# POWER.net
KiCad netlist of a schematic drawn in Altium Designer
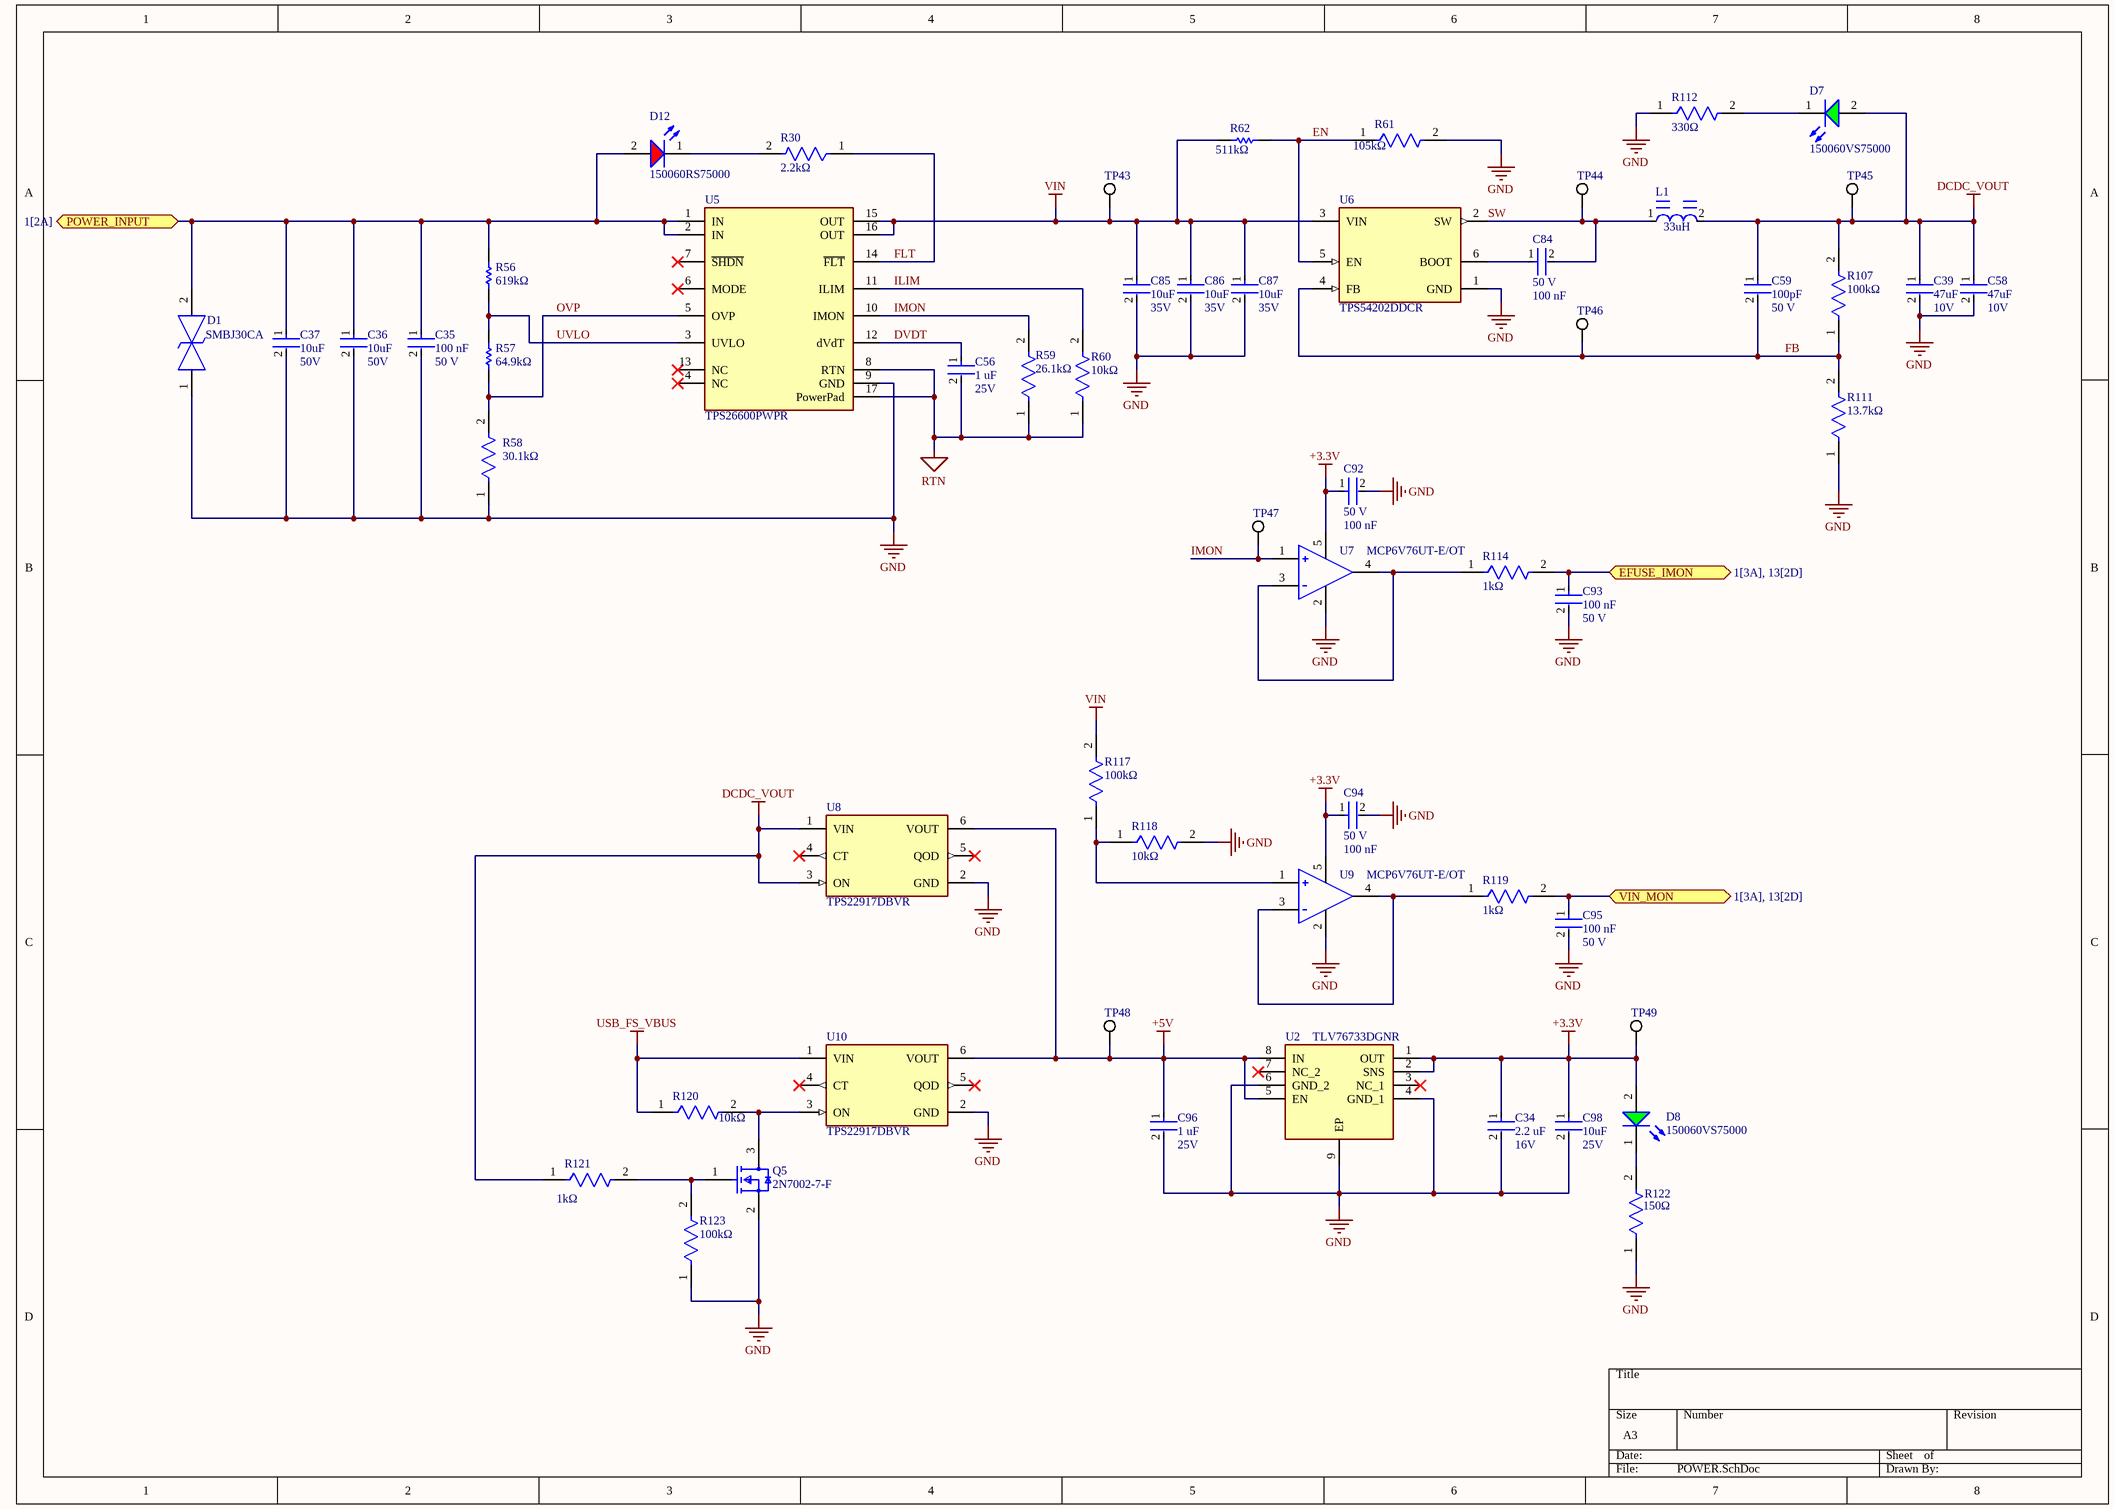
[diagram p0: POWER.SchDoc]

(export (version "E")
  (design (tool "Eeschema 10.0.6"))
  (components
    (comp (ref "C34")
      (value "CL10A225KO8NNNC")
      (footprint "FP-CL10-IPC_B")
      (description "Cap Ceramic 2.2uF 16V X5R ±10% Pad SMD 0603 +85°C T/R")
      (fields
        (field (name "CAPACITANCE") "2.2 uF")
        (field (name "VOLTAGE RATING") "16V")
        (field (name "TOLERANCE") "10%")
        (field (name "VOLTAGE") "16V")
      )
      (libsource (lib "Altium Content Vault") (part "b4654b650e69147ec39a6b967a45e02"))
    )
    (comp (ref "C35")
      (value "100 nF")
      (footprint "FP-C0603C-CF-IPC_B")
      (description "CAP CER 0.1UF 50V 20% X7R 0603")
      (fields
        (field (name "VOLTAGE RATING") "50 V")
        (field (name "MANUFACTURER PART NUMBER") "C0603C104M5RACTU")
        (field (name "MANUFACTURER") "KEMET")
      )
      (libsource (lib "Altium Content Vault") (part "b4654b650e69147ec39a6b967a45e02"))
    )
    (comp (ref "C36")
      (value "CL31A106KBHNNNE")
      (footprint "FP-CL31-IPC_B")
      (description "CAP CER 10UF 50V X5R 1206")
      (fields
        (field (name "TOLERANCE") "10%")
        (field (name "MANUFACTURER") "Samsung")
        (field (name "VOLTAGE") "50V")
        (field (name "CAPACITANCE") "10uF")
      )
      (libsource (lib "Altium Content Vault") (part "11868f565c42a9108669ba33697ecf6"))
    )
    (comp (ref "C37")
      (value "CL31A106KBHNNNE")
      (footprint "FP-CL31-IPC_B")
      (description "CAP CER 10UF 50V X5R 1206")
      (fields
        (field (name "TOLERANCE") "10%")
        (field (name "MANUFACTURER") "Samsung")
        (field (name "VOLTAGE") "50V")
        (field (name "CAPACITANCE") "10uF")
      )
      (libsource (lib "Altium Content Vault") (part "11868f565c42a9108669ba33697ecf6"))
    )
    (comp (ref "C39")
      (value "GRM32ER71A476KE15L")
      (footprint "FP-GRM32E-0_3-0_2-IPC_B")
      (description "Chip Multilayer Ceramic Capacitors for General Purpose, 1210, 47uF, X7R, 15%, 10%, 10V")
      (fields
        (field (name "VOLTAGE RATING") "10V")
        (field (name "TOLERANCE") "10%")
        (field (name "VOLTAGE") "10V")
        (field (name "CAPACITANCE") "47uF")
      )
      (libsource (lib "Altium Content Vault") (part "02cd4be3c70576c341d710602a673aa"))
    )
    (comp (ref "C56")
      (value "GCM188R71E105KA64D")
      (footprint "FP-GCM188-0_1-IPC_B")
      (fields
        (field (name "TOLERANCE") "10%")
        (field (name "CAPACITANCE") "1 uF")
        (field (name "VOLTAGE RATING") "25V")
        (field (name "VOLTAGE") "25V")
      )
      (libsource (lib "Altium Content Vault") (part "02cd4be3c70576c341d710602a673aa"))
    )
    (comp (ref "C58")
      (value "GRM32ER71A476KE15L")
      (footprint "FP-GRM32E-0_3-0_2-IPC_B")
      (description "Chip Multilayer Ceramic Capacitors for General Purpose, 1210, 47uF, X7R, 15%, 10%, 10V")
      (fields
        (field (name "VOLTAGE RATING") "10V")
        (field (name "TOLERANCE") "10%")
        (field (name "VOLTAGE") "10V")
        (field (name "CAPACITANCE") "47uF")
      )
      (libsource (lib "Altium Content Vault") (part "02cd4be3c70576c341d710602a673aa"))
    )
    (comp (ref "C59")
      (value "C0603C101J5GACTU")
      (footprint "FP-C0603C-CF-IPC_B")
      (description "CAP CER 100PF 50V C0G/NP0 0603")
      (fields
        (field (name "VOLTAGE RATING") "50 V")
        (field (name "TOLERANCE") "0.05")
        (field (name "MANUFACTURER") "KEMET")
        (field (name "CAPACITANCE") "100pF")
      )
      (libsource (lib "Altium Content Vault") (part "b4654b650e69147ec39a6b967a45e02"))
    )
    (comp (ref "C84")
      (value "100 nF")
      (footprint "FP-C0603C-CF-IPC_B")
      (description "CAP CER 0.1UF 50V 20% X7R 0603")
      (fields
        (field (name "VOLTAGE RATING") "50 V")
        (field (name "MANUFACTURER PART NUMBER") "C0603C104M5RACTU")
        (field (name "MANUFACTURER") "KEMET")
      )
      (libsource (lib "Altium Content Vault") (part "b4654b650e69147ec39a6b967a45e02"))
    )
    (comp (ref "C85")
      (value "GRM21BR6YA106KE43L")
      (footprint "FP-GRM21B-0_2-e0_2_0_7-IPC_B")
      (description "Chip Multilayer Ceramic Capacitors for General Purpose, 0805, 10uF, X5R, 15%, 10%, 35V")
      (fields
        (field (name "TOLERANCE") "10%")
        (field (name "CAPACITANCE") "10uF")
        (field (name "VOLTAGE RATING") "35V")
      )
      (libsource (lib "Altium Content Vault") (part "b4654b650e69147ec39a6b967a45e02"))
    )
    (comp (ref "C86")
      (value "GRM21BR6YA106KE43L")
      (footprint "FP-GRM21B-0_2-e0_2_0_7-IPC_B")
      (description "Chip Multilayer Ceramic Capacitors for General Purpose, 0805, 10uF, X5R, 15%, 10%, 35V")
      (fields
        (field (name "TOLERANCE") "10%")
        (field (name "CAPACITANCE") "10uF")
        (field (name "VOLTAGE RATING") "35V")
      )
      (libsource (lib "Altium Content Vault") (part "b4654b650e69147ec39a6b967a45e02"))
    )
    (comp (ref "C87")
      (value "GRM21BR6YA106KE43L")
      (footprint "FP-GRM21B-0_2-e0_2_0_7-IPC_B")
      (description "Chip Multilayer Ceramic Capacitors for General Purpose, 0805, 10uF, X5R, 15%, 10%, 35V")
      (fields
        (field (name "TOLERANCE") "10%")
        (field (name "CAPACITANCE") "10uF")
        (field (name "VOLTAGE RATING") "35V")
      )
      (libsource (lib "Altium Content Vault") (part "b4654b650e69147ec39a6b967a45e02"))
    )
    (comp (ref "C92")
      (value "100 nF")
      (footprint "FP-C0603C-CF-IPC_B")
      (description "CAP CER 0.1UF 50V 20% X7R 0603")
      (fields
        (field (name "VOLTAGE RATING") "50 V")
        (field (name "MANUFACTURER PART NUMBER") "C0603C104M5RACTU")
        (field (name "MANUFACTURER") "KEMET")
      )
      (libsource (lib "Altium Content Vault") (part "b4654b650e69147ec39a6b967a45e02"))
    )
    (comp (ref "C93")
      (value "100 nF")
      (footprint "FP-C0603C-CF-IPC_B")
      (description "CAP CER 0.1UF 50V 20% X7R 0603")
      (fields
        (field (name "VOLTAGE RATING") "50 V")
        (field (name "MANUFACTURER PART NUMBER") "C0603C104M5RACTU")
        (field (name "MANUFACTURER") "KEMET")
      )
      (libsource (lib "Altium Content Vault") (part "b4654b650e69147ec39a6b967a45e02"))
    )
    (comp (ref "C94")
      (value "100 nF")
      (footprint "FP-C0603C-CF-IPC_B")
      (description "CAP CER 0.1UF 50V 20% X7R 0603")
      (fields
        (field (name "VOLTAGE RATING") "50 V")
        (field (name "MANUFACTURER PART NUMBER") "C0603C104M5RACTU")
        (field (name "MANUFACTURER") "KEMET")
      )
      (libsource (lib "Altium Content Vault") (part "b4654b650e69147ec39a6b967a45e02"))
    )
    (comp (ref "C95")
      (value "100 nF")
      (footprint "FP-C0603C-CF-IPC_B")
      (description "CAP CER 0.1UF 50V 20% X7R 0603")
      (fields
        (field (name "VOLTAGE RATING") "50 V")
        (field (name "MANUFACTURER PART NUMBER") "C0603C104M5RACTU")
        (field (name "MANUFACTURER") "KEMET")
      )
      (libsource (lib "Altium Content Vault") (part "b4654b650e69147ec39a6b967a45e02"))
    )
    (comp (ref "C96")
      (value "GCM188R71E105KA64D")
      (footprint "FP-GCM188-0_1-IPC_B")
      (fields
        (field (name "TOLERANCE") "10%")
        (field (name "CAPACITANCE") "1 uF")
        (field (name "VOLTAGE RATING") "25V")
        (field (name "VOLTAGE") "25V")
      )
      (libsource (lib "Altium Content Vault") (part "02cd4be3c70576c341d710602a673aa"))
    )
    (comp (ref "C98")
      (value "C1608X5R1E106M080AC")
      (footprint "FP-C1608-080-IPC_B")
      (description "CAP CER 10UF 25V X5R 0603")
      (fields
        (field (name "VOLTAGE RATING") "25V")
        (field (name "TOLERANCE") "20%")
        (field (name "CAPACITANCE") "10uF")
      )
      (libsource (lib "Altium Content Vault") (part "11868f565c42a9108669ba33697ecf6"))
    )
    (comp (ref "D1")
      (value "SMBJ30CA")
      (footprint "SamacSys:DIOM5436X244N")
      (description "TVS Diode (Bi-directional)")
      (fields (field (name "MOUSER PART NUMBER") "576-SMBJ30CA"))
      (libsource (lib "*") (part "SMBJ30CA"))
    )
    (comp (ref "D7")
      (value "150060VS75000")
      (footprint "WL-SMCW_0603_150060xx75000")
      (libsource (lib "Altium Content Vault") (part "LED_Green_2A-1K"))
    )
    (comp (ref "D8")
      (value "150060VS75000")
      (footprint "WL-SMCW_0603_150060xx75000")
      (libsource (lib "Altium Content Vault") (part "LED_Green_2A-1K"))
    )
    (comp (ref "D12")
      (value "150060RS75000")
      (footprint "WL-SMCW_0603_150060xx75000")
      (libsource (lib "Altium Content Vault") (part "LED_Red_2A-1K"))
    )
    (comp (ref "L1")
      (value "SRR1280-330M")
      (footprint "FP-SRR1280-MFG")
      (description "FIXED IND 33UH 3.5A 57 MOHM SMD")
      (fields (field (name "INDUCTANCE") "33uH") (field (name "TOLERANCE") "20%"))
      (libsource (lib "Altium Content Vault") (part "6d0fbef048cab01dc475e6ab11ab505"))
    )
    (comp (ref "Q5")
      (value "2N7002-7-F")
      (footprint "FP-SOT23-IPC_A")
      (description "MOSFET N-CH 60V 115MA SOT23-3")
      (fields (field (name "VOLTAGE") "60V"))
      (libsource (lib "Altium Content Vault") (part "3b9c635fedb024a5347a57b145af9cc"))
    )
    (comp (ref "R30")
      (value "AC0603FR-072K2L")
      (footprint "FP-AC0603-IPC_B")
      (description "RES 2.2KΩ 1.00% 0.1W 0603")
      (fields (field (name "TOLERANCE") "1%") (field (name "RESISTANCE") "2.2kΩ"))
      (libsource (lib "Altium Content Vault") (part "1029c3af85768c4190bb7ad29bc67b5"))
    )
    (comp (ref "R56")
      (value "ERJ-3EKF6193V")
      (footprint "RESC1608X55X30ML15T15")
      (fields (field (name "MANUFACTURER") "Panasonic") (field (name "RESISTANCE") "619kΩ"))
      (libsource (lib "Altium Content Vault") (part "RES"))
    )
    (comp (ref "R57")
      (value "ERJ-3EKF6492V")
      (footprint "RESC1608X55X30ML15T15")
      (fields (field (name "MANUFACTURER") "Panasonic") (field (name "RESISTANCE") "64.9kΩ"))
      (libsource (lib "Altium Content Vault") (part "RES"))
    )
    (comp (ref "R58")
      (value "ERJ-3EKF3012V")
      (footprint "FP-ERJ3EK-IPC_B")
      (description "RES SMD 30.1K OHM 1% 1/10W 0603")
      (fields (field (name "TOLERANCE") "1%") (field (name "RESISTANCE") "30.1kΩ"))
      (libsource (lib "Altium Content Vault") (part "1029c3af85768c4190bb7ad29bc67b5"))
    )
    (comp (ref "R59")
      (value "CRCW060326K1FKEA")
      (footprint "FP-CRCW0603-e3-IPC_B")
      (description "RES Thick Film, 26.1kΩ, 1%, 0.1W, 100ppm/°C, 0603")
      (fields (field (name "RESISTANCE") "26.1kΩ") (field (name "TOLERANCE") "1%"))
      (libsource (lib "Altium Content Vault") (part "1029c3af85768c4190bb7ad29bc67b5"))
    )
    (comp (ref "R60")
      (value "RC0603FR-0710KL")
      (footprint "FP-RC0603-0_55-IPC_B")
      (description "RES 10K OHM 1% 1/10W 0603")
      (fields (field (name "TOLERANCE") "1%") (field (name "RESISTANCE") "10kΩ"))
      (libsource (lib "Altium Content Vault") (part "1029c3af85768c4190bb7ad29bc67b5"))
    )
    (comp (ref "R61")
      (value "RC0603FR-07105KL")
      (footprint "FP-RC0603-0_55-IPC_B")
      (description "RES SMD 105K OHM 1% 1/10W 0603")
      (fields (field (name "RESISTANCE") "105kΩ") (field (name "TOLERANCE") "1%"))
      (libsource (lib "Altium Content Vault") (part "1029c3af85768c4190bb7ad29bc67b5"))
    )
    (comp (ref "R62")
      (value "RC0603FR-07511KL")
      (footprint "RESC1608X55X25ML10T15")
      (fields (field (name "MANUFACTURER") "Yageo") (field (name "RESISTANCE") "511kΩ"))
      (libsource (lib "Altium Content Vault") (part "RES"))
    )
    (comp (ref "R107")
      (value "CRCW0603100KFKEC")
      (footprint "FP-CRCW0603-e3-IPC_B")
      (description "RES Thick Film, 100kΩ, 1%, 0.1W, 100ppm/°C, 0603")
      (fields (field (name "RESISTANCE") "100kΩ") (field (name "TOLERANCE") "1%"))
      (libsource (lib "Altium Content Vault") (part "1029c3af85768c4190bb7ad29bc67b5"))
    )
    (comp (ref "R111")
      (value "ERJ-3EKF1372V")
      (footprint "FP-ERJ3EK-IPC_B")
      (fields (field (name "RESISTANCE") "13.7kΩ") (field (name "TOLERANCE") "1%"))
      (libsource (lib "Altium Content Vault") (part "1029c3af85768c4190bb7ad29bc67b5"))
    )
    (comp (ref "R112")
      (value "CRCW0603330RFKEA")
      (footprint "FP-CRCW0603-e3-MFG")
      (description "RES Thick Film, 330Ω, 1%, 0.1W, 100ppm/°C, 0603")
      (fields (field (name "TOLERANCE") "1%") (field (name "RESISTANCE") "330Ω"))
      (libsource (lib "Altium Content Vault") (part "1029c3af85768c4190bb7ad29bc67b5"))
    )
    (comp (ref "R114")
      (value "AC0603FR-071KL")
      (footprint "FP-AC0603-IPC_B")
      (description "RES 1kΩ 1.00% 0.1W 0603")
      (fields (field (name "TOLERANCE") "1%") (field (name "RESISTANCE") "1kΩ"))
      (libsource (lib "Altium Content Vault") (part "1029c3af85768c4190bb7ad29bc67b5"))
    )
    (comp (ref "R117")
      (value "CRCW0603100KFKEC")
      (footprint "FP-CRCW0603-e3-IPC_B")
      (description "RES Thick Film, 100kΩ, 1%, 0.1W, 100ppm/°C, 0603")
      (fields (field (name "RESISTANCE") "100kΩ") (field (name "TOLERANCE") "1%"))
      (libsource (lib "Altium Content Vault") (part "1029c3af85768c4190bb7ad29bc67b5"))
    )
    (comp (ref "R118")
      (value "RC0603FR-0710KL")
      (footprint "FP-RC0603-0_55-IPC_B")
      (description "RES 10K OHM 1% 1/10W 0603")
      (fields (field (name "TOLERANCE") "1%") (field (name "RESISTANCE") "10kΩ"))
      (libsource (lib "Altium Content Vault") (part "1029c3af85768c4190bb7ad29bc67b5"))
    )
    (comp (ref "R119")
      (value "AC0603FR-071KL")
      (footprint "FP-AC0603-IPC_B")
      (description "RES 1kΩ 1.00% 0.1W 0603")
      (fields (field (name "TOLERANCE") "1%") (field (name "RESISTANCE") "1kΩ"))
      (libsource (lib "Altium Content Vault") (part "1029c3af85768c4190bb7ad29bc67b5"))
    )
    (comp (ref "R120")
      (value "RC0603FR-0710KL")
      (footprint "FP-RC0603-0_55-IPC_B")
      (description "RES 10K OHM 1% 1/10W 0603")
      (fields (field (name "TOLERANCE") "1%") (field (name "RESISTANCE") "10kΩ"))
      (libsource (lib "Altium Content Vault") (part "1029c3af85768c4190bb7ad29bc67b5"))
    )
    (comp (ref "R121")
      (value "AC0603FR-071KL")
      (footprint "FP-AC0603-IPC_B")
      (description "RES 1kΩ 1.00% 0.1W 0603")
      (fields (field (name "TOLERANCE") "1%") (field (name "RESISTANCE") "1kΩ"))
      (libsource (lib "Altium Content Vault") (part "1029c3af85768c4190bb7ad29bc67b5"))
    )
    (comp (ref "R122")
      (value "CRCW0603150RFKEA")
      (footprint "FP-CRCW0603-e3-IPC_B")
      (description "RES Thick Film, 150Ω, 1%, 0.1W, 100ppm/°C, 0603")
      (fields (field (name "TOLERANCE") "1%") (field (name "RESISTANCE") "150Ω"))
      (libsource (lib "Altium Content Vault") (part "1029c3af85768c4190bb7ad29bc67b5"))
    )
    (comp (ref "R123")
      (value "CRCW0603100KFKEC")
      (footprint "FP-CRCW0603-e3-IPC_B")
      (description "RES Thick Film, 100kΩ, 1%, 0.1W, 100ppm/°C, 0603")
      (fields (field (name "RESISTANCE") "100kΩ") (field (name "TOLERANCE") "1%"))
      (libsource (lib "Altium Content Vault") (part "1029c3af85768c4190bb7ad29bc67b5"))
    )
    (comp (ref "TP43")
      (value "5019")
      (footprint "KSTN-5019_V")
      (description "Test Point, 1 Position SMD, RoHS, Tape and Reel")
      (libsource (lib "Altium Content Vault") (part "TESTPOINT_WHITE"))
    )
    (comp (ref "TP44")
      (value "5019")
      (footprint "KSTN-5019_V")
      (description "Test Point, 1 Position SMD, RoHS, Tape and Reel")
      (libsource (lib "Altium Content Vault") (part "TESTPOINT_WHITE"))
    )
    (comp (ref "TP45")
      (value "5019")
      (footprint "KSTN-5019_V")
      (description "Test Point, 1 Position SMD, RoHS, Tape and Reel")
      (libsource (lib "Altium Content Vault") (part "TESTPOINT_WHITE"))
    )
    (comp (ref "TP46")
      (value "5019")
      (footprint "KSTN-5019_V")
      (description "Test Point, 1 Position SMD, RoHS, Tape and Reel")
      (libsource (lib "Altium Content Vault") (part "TESTPOINT_WHITE"))
    )
    (comp (ref "TP47")
      (value "5019")
      (footprint "KSTN-5019_V")
      (description "Test Point, 1 Position SMD, RoHS, Tape and Reel")
      (libsource (lib "Altium Content Vault") (part "TESTPOINT_WHITE"))
    )
    (comp (ref "TP48")
      (value "5019")
      (footprint "KSTN-5019_V")
      (description "Test Point, 1 Position SMD, RoHS, Tape and Reel")
      (libsource (lib "Altium Content Vault") (part "TESTPOINT_WHITE"))
    )
    (comp (ref "TP49")
      (value "5019")
      (footprint "KSTN-5019_V")
      (description "Test Point, 1 Position SMD, RoHS, Tape and Reel")
      (libsource (lib "Altium Content Vault") (part "TESTPOINT_WHITE"))
    )
    (comp (ref "U2")
      (value "TLV76733DGNR")
      (footprint "SamacSys:SOP65P490X110-9N")
      (description "Integrated Circuit")
      (fields (field (name "MOUSER PART NUMBER") "595-TLV76733DGNR"))
      (libsource (lib "*") (part "TLV76733DGNR"))
    )
    (comp (ref "U5")
      (value "TPS26600PWPR")
      (footprint "FP-PWP0016H-IPC_A")
      (description "IC PWR MGMT EFUSE 60V 16HTSSOP")
      (fields
        (field (name "MANUFACTURER") "Texas Instruments")
        (field (name "OCTOPART") "https://octopart.com/tps26600pwpr-texas+instruments-75302671")
      )
      (libsource (lib "Altium Content Vault") (part "280d3bfec34d6f4e646feda1cd72b11"))
    )
    (comp (ref "U6")
      (value "TPS54202DDCR")
      (footprint "FP-DDC0006A-MFG")
      (description "IC REG BUCK ADJ 2A TSOT23-6")
      (libsource (lib "Altium Content Vault") (part "35c2d3f1afc239a386b2ba50eead654"))
    )
    (comp (ref "U7")
      (value "MCP6V76UT-E/OT")
      (footprint "FP-C04-091-OT-MFG")
      (description "MCP6V76UT-E/OT Operational Amplifier Zero-Drift 170uA 2MHz 2V to 5.5V 1V/us 5-Pin SOT-23 T/R")
      (libsource (lib "Altium Content Vault") (part "b4f880975ad20504bd736d7a3cbcf65"))
    )
    (comp (ref "U8")
      (value "TPS22917DBVR")
      (footprint "FP-DBV0006A-MFG")
      (description "IC PWR SWITCH P-CHAN 1:1 SOT23-6")
      (libsource (lib "Altium Content Vault") (part "79ac4b3a8af48598f911740ea3eee0a"))
    )
    (comp (ref "U9")
      (value "MCP6V76UT-E/OT")
      (footprint "FP-C04-091-OT-MFG")
      (description "MCP6V76UT-E/OT Operational Amplifier Zero-Drift 170uA 2MHz 2V to 5.5V 1V/us 5-Pin SOT-23 T/R")
      (libsource (lib "Altium Content Vault") (part "b4f880975ad20504bd736d7a3cbcf65"))
    )
    (comp (ref "U10")
      (value "TPS22917DBVR")
      (footprint "FP-DBV0006A-MFG")
      (description "IC PWR SWITCH P-CHAN 1:1 SOT23-6")
      (libsource (lib "Altium Content Vault") (part "79ac4b3a8af48598f911740ea3eee0a"))
    )
  )
  (nets
    (net (code "1") (name "+3.3V") (class "Default")
      (node (ref "C34") (pin "1") (pinfunction "1_1") (pintype "passive"))
      (node (ref "C92") (pin "1") (pinfunction "1_1") (pintype "passive"))
      (node (ref "C94") (pin "1") (pinfunction "1_1") (pintype "passive"))
      (node (ref "C98") (pin "1") (pinfunction "1_1") (pintype "passive"))
      (node (ref "D8") (pin "2") (pinfunction "A_2") (pintype "passive"))
      (node (ref "TP49") (pin "1") (pinfunction "1_1") (pintype "passive"))
      (node (ref "U2") (pin "1") (pinfunction "OUT_1") (pintype "passive"))
      (node (ref "U2") (pin "2") (pinfunction "SNS_2") (pintype "passive"))
      (node (ref "U7") (pin "5") (pinfunction "VDD_5") (pintype "power_in"))
      (node (ref "U9") (pin "5") (pinfunction "VDD_5") (pintype "power_in"))
    )
    (net (code "2") (name "+5V") (class "Default")
      (node (ref "C96") (pin "1") (pinfunction "1_1") (pintype "passive"))
      (node (ref "TP48") (pin "1") (pinfunction "1_1") (pintype "passive"))
      (node (ref "U10") (pin "6") (pinfunction "VOUT_6") (pintype "power_in"))
      (node (ref "U2") (pin "5") (pinfunction "EN_5") (pintype "passive"))
      (node (ref "U2") (pin "8") (pinfunction "IN_8") (pintype "passive"))
      (node (ref "U8") (pin "6") (pinfunction "VOUT_6") (pintype "power_in"))
    )
    (net (code "3") (name "/DVDT") (class "Default")
      (node (ref "C56") (pin "1") (pinfunction "1_1") (pintype "passive"))
      (node (ref "U5") (pin "12") (pinfunction "dVdT_12") (pintype "passive"))
    )
    (net (code "4") (name "/EFUSE_IMON") (class "Default")
      (node (ref "C93") (pin "1") (pinfunction "1_1") (pintype "passive"))
      (node (ref "R114") (pin "2") (pinfunction "2_2") (pintype "passive"))
    )
    (net (code "5") (name "/EN") (class "Default")
      (node (ref "R61") (pin "1") (pinfunction "1_1") (pintype "passive"))
      (node (ref "R62") (pin "2") (pinfunction "2_2") (pintype "passive"))
      (node (ref "U6") (pin "5") (pinfunction "EN_5") (pintype "input"))
    )
    (net (code "6") (name "/FB") (class "Default")
      (node (ref "C59") (pin "2") (pinfunction "2_2") (pintype "passive"))
      (node (ref "R107") (pin "1") (pinfunction "1_1") (pintype "passive"))
      (node (ref "R111") (pin "2") (pinfunction "2_2") (pintype "passive"))
      (node (ref "TP46") (pin "1") (pinfunction "1_1") (pintype "passive"))
      (node (ref "U6") (pin "4") (pinfunction "FB_4") (pintype "input"))
    )
    (net (code "7") (name "/FLT") (class "Default")
      (node (ref "R30") (pin "1") (pinfunction "1_1") (pintype "passive"))
      (node (ref "U5") (pin "14") (pinfunction "~{FLT}_14") (pintype "passive"))
    )
    (net (code "8") (name "/ILIM") (class "Default")
      (node (ref "R60") (pin "2") (pinfunction "2_2") (pintype "passive"))
      (node (ref "U5") (pin "11") (pinfunction "ILIM_11") (pintype "passive"))
    )
    (net (code "9") (name "/IMON") (class "Default")
      (node (ref "R59") (pin "2") (pinfunction "2_2") (pintype "passive"))
      (node (ref "TP47") (pin "1") (pinfunction "1_1") (pintype "passive"))
      (node (ref "U5") (pin "10") (pinfunction "IMON_10") (pintype "passive"))
      (node (ref "U7") (pin "1") (pinfunction "VIN+_1") (pintype "tri_state"))
    )
    (net (code "10") (name "/OVP") (class "Default")
      (node (ref "R57") (pin "1") (pinfunction "1_1") (pintype "passive"))
      (node (ref "R58") (pin "2") (pinfunction "2_2") (pintype "passive"))
      (node (ref "U5") (pin "5") (pinfunction "OVP_5") (pintype "passive"))
    )
    (net (code "11") (name "/POWER_INPUT") (class "Default")
      (node (ref "C35") (pin "1") (pinfunction "1_1") (pintype "passive"))
      (node (ref "C36") (pin "1") (pinfunction "1_1") (pintype "passive"))
      (node (ref "C37") (pin "1") (pinfunction "1_1") (pintype "passive"))
      (node (ref "D1") (pin "2") (pinfunction "2_2") (pintype "passive"))
      (node (ref "D12") (pin "2") (pinfunction "A_2") (pintype "passive"))
      (node (ref "R56") (pin "2") (pinfunction "2_2") (pintype "passive"))
      (node (ref "U5") (pin "1") (pinfunction "IN_1") (pintype "passive"))
      (node (ref "U5") (pin "2") (pinfunction "IN_2") (pintype "passive"))
    )
    (net (code "12") (name "/SW") (class "Default")
      (node (ref "C84") (pin "2") (pinfunction "2_2") (pintype "passive"))
      (node (ref "L1") (pin "1") (pinfunction "1_1") (pintype "passive"))
      (node (ref "TP44") (pin "1") (pinfunction "1_1") (pintype "passive"))
      (node (ref "U6") (pin "2") (pinfunction "SW_2") (pintype "output"))
    )
    (net (code "13") (name "/UVLO") (class "Default")
      (node (ref "R56") (pin "1") (pinfunction "1_1") (pintype "passive"))
      (node (ref "R57") (pin "2") (pinfunction "2_2") (pintype "passive"))
      (node (ref "U5") (pin "3") (pinfunction "UVLO_3") (pintype "passive"))
    )
    (net (code "14") (name "/VIN_MON") (class "Default")
      (node (ref "C95") (pin "1") (pinfunction "1_1") (pintype "passive"))
      (node (ref "R119") (pin "2") (pinfunction "2_2") (pintype "passive"))
    )
    (net (code "15") (name "DCDC_VOUT") (class "Default")
      (node (ref "C39") (pin "1") (pinfunction "1_1") (pintype "passive"))
      (node (ref "C58") (pin "1") (pinfunction "1_1") (pintype "passive"))
      (node (ref "C59") (pin "1") (pinfunction "1_1") (pintype "passive"))
      (node (ref "D7") (pin "2") (pinfunction "A_2") (pintype "passive"))
      (node (ref "L1") (pin "2") (pinfunction "2_2") (pintype "passive"))
      (node (ref "R107") (pin "2") (pinfunction "2_2") (pintype "passive"))
      (node (ref "R121") (pin "1") (pinfunction "1_1") (pintype "passive"))
      (node (ref "TP45") (pin "1") (pinfunction "1_1") (pintype "passive"))
      (node (ref "U8") (pin "1") (pinfunction "VIN_1") (pintype "passive"))
      (node (ref "U8") (pin "3") (pinfunction "ON_3") (pintype "input"))
    )
    (net (code "16") (name "GND") (class "Default")
      (node (ref "C34") (pin "2") (pinfunction "2_2") (pintype "passive"))
      (node (ref "C35") (pin "2") (pinfunction "2_2") (pintype "passive"))
      (node (ref "C36") (pin "2") (pinfunction "2_2") (pintype "passive"))
      (node (ref "C37") (pin "2") (pinfunction "2_2") (pintype "passive"))
      (node (ref "C39") (pin "2") (pinfunction "2_2") (pintype "passive"))
      (node (ref "C58") (pin "2") (pinfunction "2_2") (pintype "passive"))
      (node (ref "C85") (pin "2") (pinfunction "2_2") (pintype "passive"))
      (node (ref "C86") (pin "2") (pinfunction "2_2") (pintype "passive"))
      (node (ref "C87") (pin "2") (pinfunction "2_2") (pintype "passive"))
      (node (ref "C92") (pin "2") (pinfunction "2_2") (pintype "passive"))
      (node (ref "C93") (pin "2") (pinfunction "2_2") (pintype "passive"))
      (node (ref "C94") (pin "2") (pinfunction "2_2") (pintype "passive"))
      (node (ref "C95") (pin "2") (pinfunction "2_2") (pintype "passive"))
      (node (ref "C96") (pin "2") (pinfunction "2_2") (pintype "passive"))
      (node (ref "C98") (pin "2") (pinfunction "2_2") (pintype "passive"))
      (node (ref "D1") (pin "1") (pinfunction "1_1") (pintype "passive"))
      (node (ref "Q5") (pin "2") (pinfunction "S_2") (pintype "passive"))
      (node (ref "R111") (pin "1") (pinfunction "1_1") (pintype "passive"))
      (node (ref "R112") (pin "1") (pinfunction "1_1") (pintype "passive"))
      (node (ref "R118") (pin "2") (pinfunction "2_2") (pintype "passive"))
      (node (ref "R122") (pin "1") (pinfunction "1_1") (pintype "passive"))
      (node (ref "R123") (pin "1") (pinfunction "1_1") (pintype "passive"))
      (node (ref "R58") (pin "1") (pinfunction "1_1") (pintype "passive"))
      (node (ref "R61") (pin "2") (pinfunction "2_2") (pintype "passive"))
      (node (ref "U10") (pin "2") (pinfunction "GND_2") (pintype "power_in"))
      (node (ref "U2") (pin "4") (pinfunction "GND_1_4") (pintype "passive"))
      (node (ref "U2") (pin "6") (pinfunction "GND_2_6") (pintype "passive"))
      (node (ref "U2") (pin "9") (pinfunction "EP_9") (pintype "passive"))
      (node (ref "U5") (pin "9") (pinfunction "GND_9") (pintype "power_in"))
      (node (ref "U6") (pin "1") (pinfunction "GND_1") (pintype "power_in"))
      (node (ref "U7") (pin "2") (pinfunction "VSS_2") (pintype "power_in"))
      (node (ref "U8") (pin "2") (pinfunction "GND_2") (pintype "power_in"))
      (node (ref "U9") (pin "2") (pinfunction "VSS_2") (pintype "power_in"))
    )
    (net (code "17") (name "Net-(D7-K)") (class "Default")
      (node (ref "D7") (pin "1") (pinfunction "K_1") (pintype "passive"))
      (node (ref "R112") (pin "2") (pinfunction "2_2") (pintype "passive"))
    )
    (net (code "18") (name "Net-(D8-K)") (class "Default")
      (node (ref "D8") (pin "1") (pinfunction "K_1") (pintype "passive"))
      (node (ref "R122") (pin "2") (pinfunction "2_2") (pintype "passive"))
    )
    (net (code "19") (name "Net-(D12-K)") (class "Default")
      (node (ref "D12") (pin "1") (pinfunction "K_1") (pintype "passive"))
      (node (ref "R30") (pin "2") (pinfunction "2_2") (pintype "passive"))
    )
    (net (code "20") (name "Net-(Q5-D)") (class "Default")
      (node (ref "Q5") (pin "3") (pinfunction "D_3") (pintype "passive"))
      (node (ref "R120") (pin "2") (pinfunction "2_2") (pintype "passive"))
      (node (ref "U10") (pin "3") (pinfunction "ON_3") (pintype "input"))
    )
    (net (code "21") (name "Net-(Q5-G)") (class "Default")
      (node (ref "Q5") (pin "1") (pinfunction "G_1") (pintype "passive"))
      (node (ref "R121") (pin "2") (pinfunction "2_2") (pintype "passive"))
      (node (ref "R123") (pin "2") (pinfunction "2_2") (pintype "passive"))
    )
    (net (code "22") (name "Net-(U6-BOOT)") (class "Default")
      (node (ref "C84") (pin "1") (pinfunction "1_1") (pintype "passive"))
      (node (ref "U6") (pin "6") (pinfunction "BOOT_6") (pintype "passive"))
    )
    (net (code "23") (name "Net-(U7-VIN-)") (class "Default")
      (node (ref "R114") (pin "1") (pinfunction "1_1") (pintype "passive"))
      (node (ref "U7") (pin "3") (pinfunction "VIN-_3") (pintype "tri_state"))
      (node (ref "U7") (pin "4") (pinfunction "VOUT_4") (pintype "passive"))
    )
    (net (code "24") (name "Net-(U9-VIN+)") (class "Default")
      (node (ref "R117") (pin "1") (pinfunction "1_1") (pintype "passive"))
      (node (ref "R118") (pin "1") (pinfunction "1_1") (pintype "passive"))
      (node (ref "U9") (pin "1") (pinfunction "VIN+_1") (pintype "tri_state"))
    )
    (net (code "25") (name "Net-(U9-VIN-)") (class "Default")
      (node (ref "R119") (pin "1") (pinfunction "1_1") (pintype "passive"))
      (node (ref "U9") (pin "3") (pinfunction "VIN-_3") (pintype "tri_state"))
      (node (ref "U9") (pin "4") (pinfunction "VOUT_4") (pintype "passive"))
    )
    (net (code "26") (name "RTN") (class "Default")
      (node (ref "C56") (pin "2") (pinfunction "2_2") (pintype "passive"))
      (node (ref "R59") (pin "1") (pinfunction "1_1") (pintype "passive"))
      (node (ref "R60") (pin "1") (pinfunction "1_1") (pintype "passive"))
      (node (ref "U5") (pin "17") (pinfunction "PowerPad_17") (pintype "power_in"))
      (node (ref "U5") (pin "8") (pinfunction "RTN_8") (pintype "power_in"))
    )
    (net (code "27") (name "USB_FS_VBUS") (class "Default")
      (node (ref "R120") (pin "1") (pinfunction "1_1") (pintype "passive"))
      (node (ref "U10") (pin "1") (pinfunction "VIN_1") (pintype "passive"))
    )
    (net (code "28") (name "VIN") (class "Default")
      (node (ref "C85") (pin "1") (pinfunction "1_1") (pintype "passive"))
      (node (ref "C86") (pin "1") (pinfunction "1_1") (pintype "passive"))
      (node (ref "C87") (pin "1") (pinfunction "1_1") (pintype "passive"))
      (node (ref "R117") (pin "2") (pinfunction "2_2") (pintype "passive"))
      (node (ref "R62") (pin "1") (pinfunction "1_1") (pintype "passive"))
      (node (ref "TP43") (pin "1") (pinfunction "1_1") (pintype "passive"))
      (node (ref "U5") (pin "15") (pinfunction "OUT_15") (pintype "power_in"))
      (node (ref "U5") (pin "16") (pinfunction "OUT_16") (pintype "power_in"))
      (node (ref "U6") (pin "3") (pinfunction "VIN_3") (pintype "power_in"))
    )
    (net (code "29") (name "unconnected-(U2-NC_1-Pad3)") (class "Default")
      (node (ref "U2") (pin "3") (pinfunction "NC_1_3") (pintype "passive+no_connect"))
    )
    (net (code "30") (name "unconnected-(U2-NC_2-Pad7)") (class "Default")
      (node (ref "U2") (pin "7") (pinfunction "NC_2_7") (pintype "passive+no_connect"))
    )
    (net (code "31") (name "unconnected-(U5-MODE-Pad6)") (class "Default")
      (node (ref "U5") (pin "6") (pinfunction "MODE_6") (pintype "passive+no_connect"))
    )
    (net (code "32") (name "unconnected-(U5-NC-Pad4)") (class "Default")
      (node (ref "U5") (pin "4") (pinfunction "NC_4") (pintype "passive+no_connect"))
    )
    (net (code "33") (name "unconnected-(U5-NC-Pad13)") (class "Default")
      (node (ref "U5") (pin "13") (pinfunction "NC_13") (pintype "passive+no_connect"))
    )
    (net (code "34") (name "unconnected-(U5-~{SHDN}-Pad7)") (class "Default")
      (node (ref "U5") (pin "7") (pinfunction "~{SHDN}_7") (pintype "passive+no_connect"))
    )
    (net (code "35") (name "unconnected-(U8-CT-Pad4)") (class "Default")
      (node (ref "U8") (pin "4") (pinfunction "CT_4") (pintype "output+no_connect"))
    )
    (net (code "36") (name "unconnected-(U8-QOD-Pad5)") (class "Default")
      (node (ref "U8") (pin "5") (pinfunction "QOD_5") (pintype "output+no_connect"))
    )
    (net (code "37") (name "unconnected-(U10-CT-Pad4)") (class "Default")
      (node (ref "U10") (pin "4") (pinfunction "CT_4") (pintype "output+no_connect"))
    )
    (net (code "38") (name "unconnected-(U10-QOD-Pad5)") (class "Default")
      (node (ref "U10") (pin "5") (pinfunction "QOD_5") (pintype "output+no_connect"))
    )
  )
)
